# PY32F002BF1xP_START.net
KiCad netlist of a schematic drawn in Altium Designer
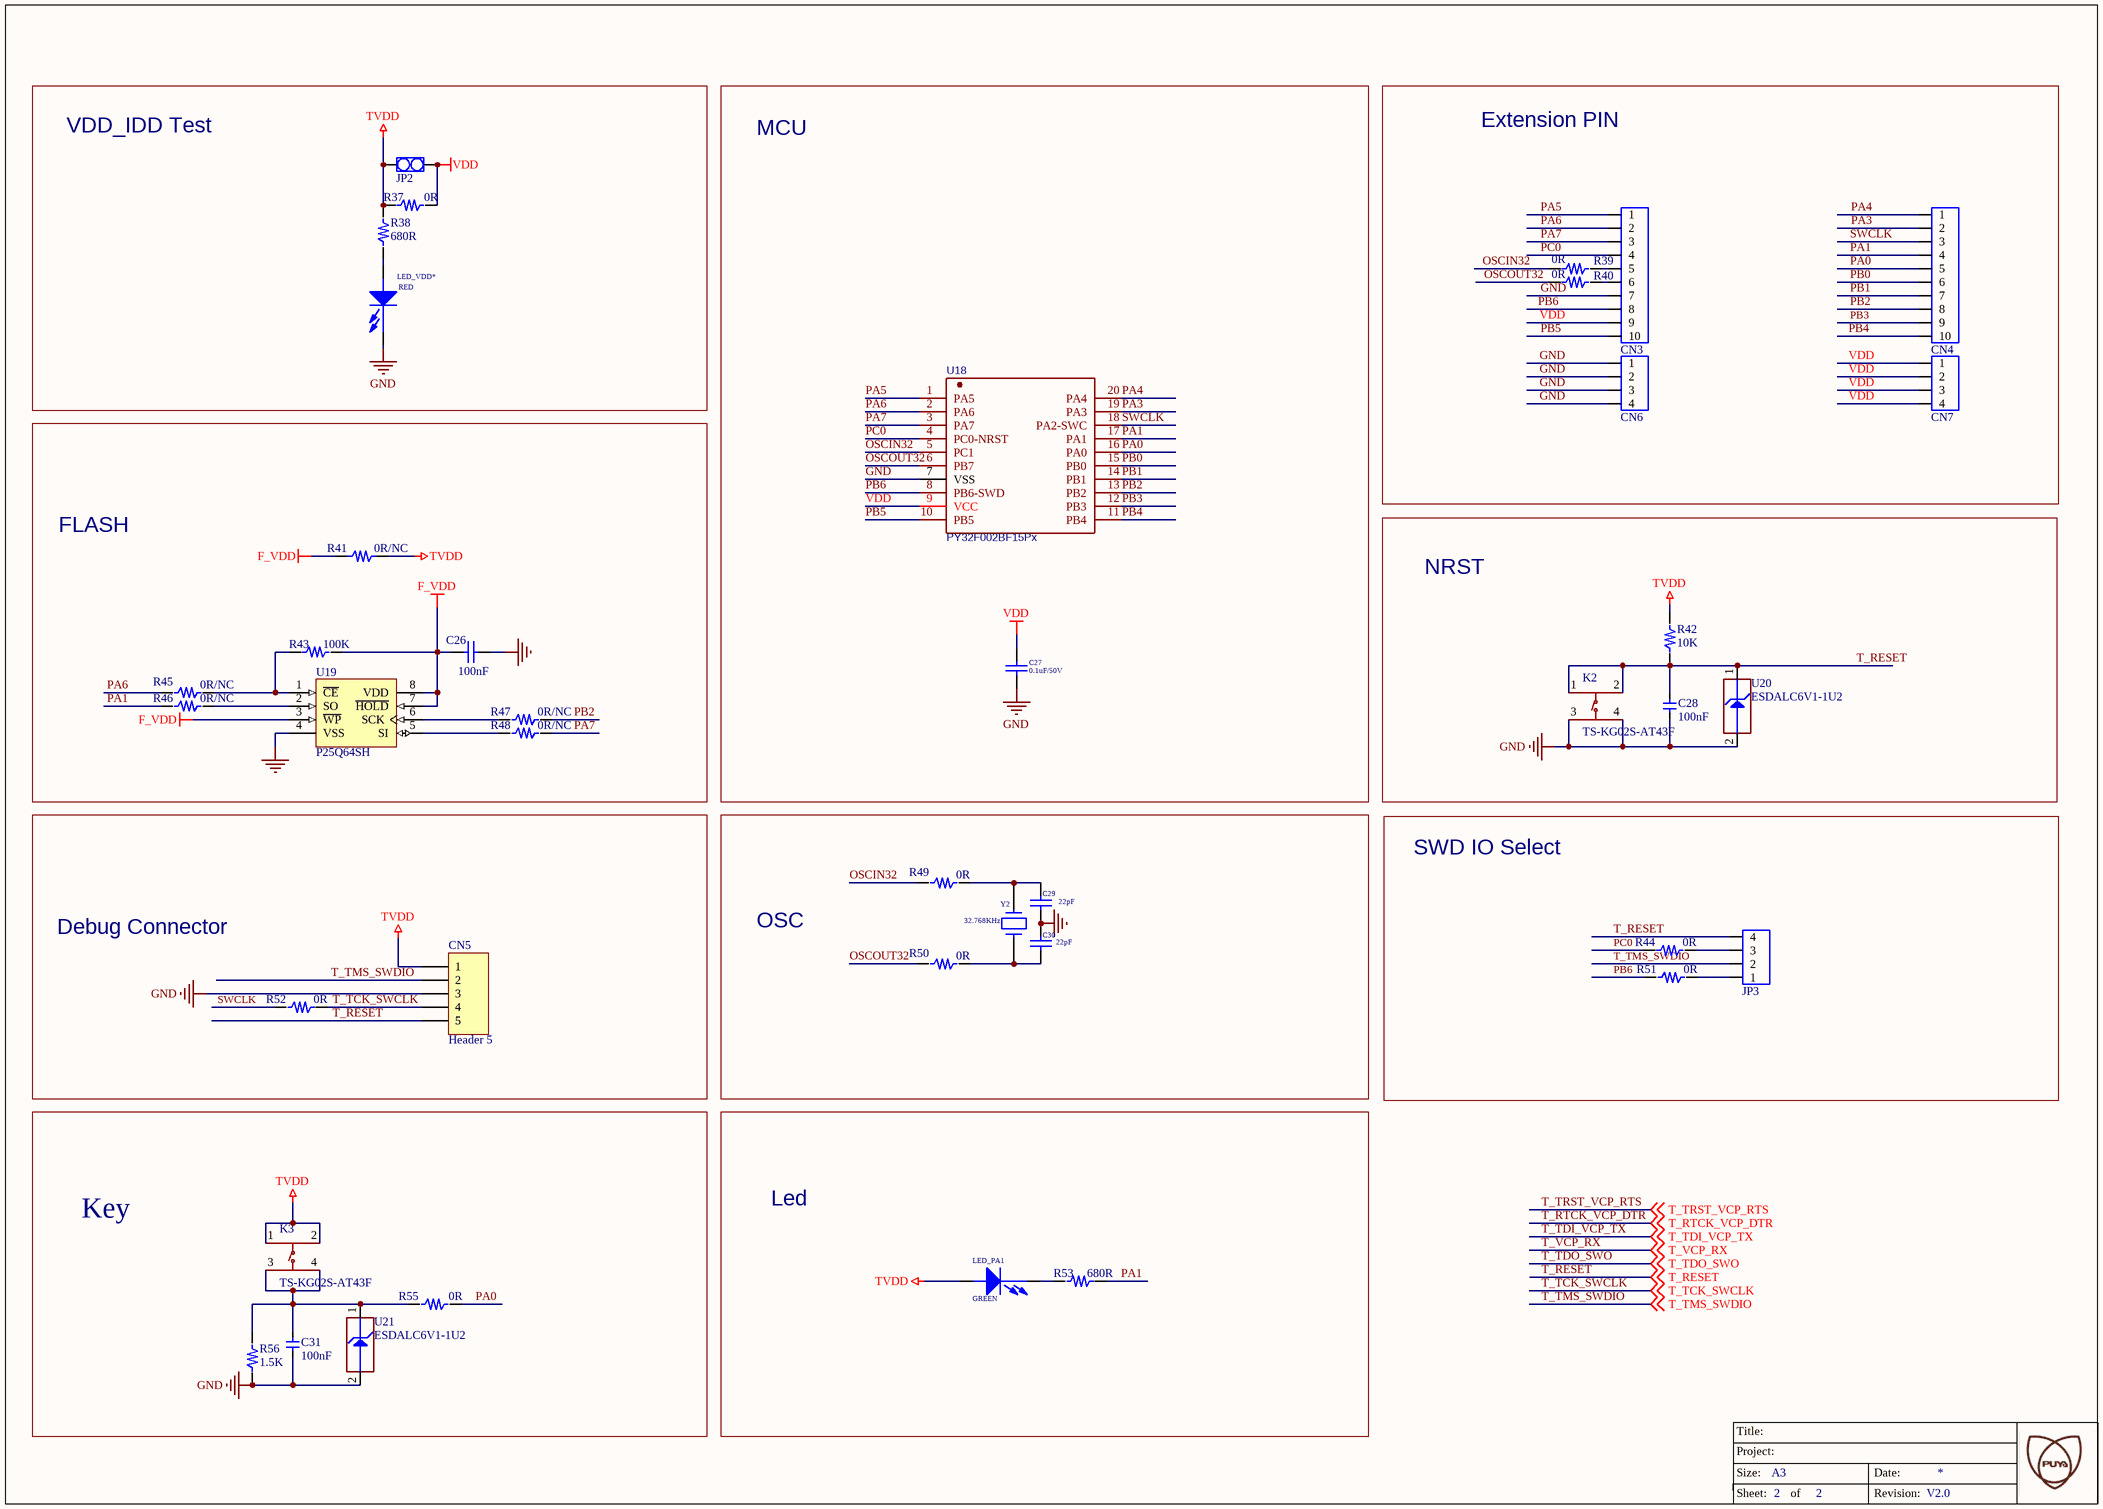
[diagram p0: PY32F002BF1xP_START.SchDoc]

(export (version "E")
  (design (tool "Eeschema 10.0.6"))
  (components
    (comp (ref "C26")
      (value "100nF")
      (footprint "C0603")
      (description "Capacitor (Semiconductor SIM Model)")
      (libsource (lib "PRO") (part "贴片高压陶瓷电容"))
    )
    (comp (ref "C27")
      (value "0.1uF/50V")
      (footprint "0603C")
      (description "Capacitor")
      (fields (field (name "PUBLISHER") "Altium Limited"))
      (libsource (lib "PY32F030_StartKit_V1.0") (part "CAP"))
    )
    (comp (ref "C28") (value "100nF") (footprint "C0603") (libsource (lib "ZqfAdLibrary") (part "C0603")))
    (comp (ref "C29")
      (value "22pF")
      (footprint "0603C")
      (description "Capacitor")
      (fields (field (name "PUBLISHER") "Altium Limited"))
      (libsource (lib "*") (part "Cap"))
    )
    (comp (ref "C30")
      (value "22pF")
      (footprint "0603C")
      (description "Capacitor")
      (fields (field (name "PUBLISHER") "Altium Limited"))
      (libsource (lib "*") (part "Cap"))
    )
    (comp (ref "C31") (value "100nF") (footprint "C0603") (libsource (lib "ZqfAdLibrary") (part "C0603")))
    (comp (ref "CN3") (value "CON10") (footprint "CON10") (libsource (lib "ZqfAdLibrary") (part "CON10")))
    (comp (ref "CN4") (value "CON10") (footprint "CON10") (libsource (lib "ZqfAdLibrary") (part "CON10")))
    (comp (ref "CN5")
      (value "Header 5")
      (footprint "HDR1X5")
      (description "Header, 5-Pin")
      (fields (field (name "PUBLISHER") "Altium Limited"))
      (libsource (lib "PY32F403x_64pin_PYLink_STK_V1.0") (part "Header 5"))
    )
    (comp (ref "CN6") (value "CON4") (footprint "CON4") (libsource (lib "ZqfAdLibrary") (part "CON4")))
    (comp (ref "CN7") (value "CON4") (footprint "CON4") (libsource (lib "ZqfAdLibrary") (part "CON4")))
    (comp (ref "JP2") (value "CON2") (footprint "CON2") (libsource (lib "ZqfAdLibrary") (part "CON2_DIP")))
    (comp (ref "JP3") (value "CON4") (footprint "CON4") (libsource (lib "ZqfAdLibrary") (part "CON4")))
    (comp (ref "K2")
      (value "TS-KG02S-AT43F")
      (footprint "SW-SMD_4P-L6.0-W6.0-P4.50-LS8.5")
      (fields (field (name "MANUFACTURER") "HANBO(汉博)"))
      (libsource (lib "altium-import") (part "root_0_TS-KG02S-AT43F_"))
    )
    (comp (ref "K3")
      (value "TS-KG02S-AT43F")
      (footprint "SW-SMD_4P-L6.0-W6.0-P4.50-LS8.5")
      (fields (field (name "MANUFACTURER") "HANBO(汉博)"))
      (libsource (lib "altium-import") (part "root_0_TS-KG02S-AT43F_"))
    )
    (comp (ref "LED_PA1")
      (value "GREEN")
      (footprint "0603_LED")
      (libsource (lib "Reliability EV board V1.0_1") (part "PDI-E803_Dup1"))
    )
    (comp (ref "LED_VDD*")
      (value "RED")
      (footprint "0603_LED")
      (libsource (lib "Reliability EV board V1.0_1") (part "PDI-E803_Dup1"))
    )
    (comp (ref "R37") (value "0R") (footprint "JP2_SMD") (libsource (lib "ZqfAdLibrary") (part "R0603")))
    (comp (ref "R38") (value "680R") (footprint "R0603") (libsource (lib "ZqfAdLibrary") (part "R0603")))
    (comp (ref "R39") (value "0R") (footprint "JP2_SMD") (libsource (lib "ZqfAdLibrary") (part "R0603")))
    (comp (ref "R40") (value "0R") (footprint "JP2_SMD") (libsource (lib "ZqfAdLibrary") (part "R0603")))
    (comp (ref "R41") (value "0R/NC") (footprint "JP2_SMD") (libsource (lib "ZqfAdLibrary") (part "R0603")))
    (comp (ref "R42") (value "10K") (footprint "R0603") (libsource (lib "ZqfAdLibrary") (part "R0603")))
    (comp (ref "R43") (value "100K") (footprint "R0603") (libsource (lib "ZqfAdLibrary") (part "R0603")))
    (comp (ref "R44") (value "0R") (footprint "JP2_SMD") (libsource (lib "ZqfAdLibrary") (part "R0603")))
    (comp (ref "R45") (value "0R/NC") (footprint "JP2_SMD") (libsource (lib "ZqfAdLibrary") (part "R0603")))
    (comp (ref "R46") (value "0R/NC") (footprint "JP2_SMD") (libsource (lib "ZqfAdLibrary") (part "R0603")))
    (comp (ref "R47") (value "0R/NC") (footprint "JP2_SMD") (libsource (lib "ZqfAdLibrary") (part "R0603")))
    (comp (ref "R48") (value "0R/NC") (footprint "JP2_SMD") (libsource (lib "ZqfAdLibrary") (part "R0603")))
    (comp (ref "R49") (value "0R") (footprint "JP2_SMD") (libsource (lib "ZqfAdLibrary") (part "R0603")))
    (comp (ref "R50") (value "0R") (footprint "JP2_SMD") (libsource (lib "ZqfAdLibrary") (part "R0603")))
    (comp (ref "R51") (value "0R") (footprint "JP2_SMD") (libsource (lib "ZqfAdLibrary") (part "R0603")))
    (comp (ref "R52") (value "0R") (footprint "JP2_SMD") (libsource (lib "ZqfAdLibrary") (part "R0603")))
    (comp (ref "R53") (value "680R") (footprint "R0603") (libsource (lib "ZqfAdLibrary") (part "R0603")))
    (comp (ref "R55") (value "0R") (footprint "JP2_SMD") (libsource (lib "ZqfAdLibrary") (part "R0603")))
    (comp (ref "R56") (value "1.5K") (footprint "R0603") (libsource (lib "ZqfAdLibrary") (part "R0603")))
    (comp (ref "U18")
      (value "PY32F002BF15Px")
      (footprint "TSSOP-20_L6.5-W4.4-P0.65-LS6.4-BL")
      (description "TSSOP20")
      (libsource (lib "Puya-MCU_V1.1") (part "PY32F002BF15Px"))
    )
    (comp (ref "U19")
      (value "P25Q64SH")
      (footprint "SOP-8P")
      (description "SST25VF010")
      (libsource (lib "PM3.00_Pro") (part "SST25VF010"))
    )
    (comp (ref "U20")
      (value "ESDALC6V1-1U2")
      (footprint "ESD_ST0201")
      (description "ESD protection 6V1")
      (fields
        (field (name "INTERNAL_PART_NUMBER") "MCD-00170")
        (field (name "MANUFACTURER") "STMICROELECTRONICS")
        (field (name "PROVIDED_BY") "Subcon")
      )
      (libsource (lib "PY32F403V1xT_START") (part "ESDALC6V1-1U2"))
    )
    (comp (ref "U21")
      (value "ESDALC6V1-1U2")
      (footprint "ESD_ST0201")
      (description "ESD protection 6V1")
      (fields
        (field (name "INTERNAL_PART_NUMBER") "MCD-00170")
        (field (name "MANUFACTURER") "STMICROELECTRONICS")
        (field (name "PROVIDED_BY") "Subcon")
      )
      (libsource (lib "PY32F403V1xT_START") (part "ESDALC6V1-1U2"))
    )
    (comp (ref "Y2")
      (value "32.768KHz")
      (footprint "CRYSTAL-SMD_L3.2-W1.5-1")
      (description "Crystal")
      (libsource (lib "PY32F002B_StartKit_V1.0") (part "CRYSTAL_1"))
    )
  )
  (nets
    (net (code "1") (name "/OSCIN32") (class "Default")
      (node (ref "R39") (pin "1") (pinfunction "1_1") (pintype "passive"))
      (node (ref "R49") (pin "2") (pinfunction "2_2") (pintype "passive"))
      (node (ref "U18") (pin "5") (pinfunction "PC1_5") (pintype "passive"))
    )
    (net (code "2") (name "/OSCOUT32") (class "Default")
      (node (ref "R40") (pin "1") (pinfunction "1_1") (pintype "passive"))
      (node (ref "R50") (pin "2") (pinfunction "2_2") (pintype "passive"))
      (node (ref "U18") (pin "6") (pinfunction "PB7_6") (pintype "passive"))
    )
    (net (code "3") (name "/PA0") (class "Default")
      (node (ref "CN4") (pin "5") (pinfunction "5_5") (pintype "passive"))
      (node (ref "R55") (pin "2") (pinfunction "2_2") (pintype "passive"))
      (node (ref "U18") (pin "16") (pinfunction "PA0_16") (pintype "passive"))
    )
    (net (code "4") (name "/PA1") (class "Default")
      (node (ref "CN4") (pin "4") (pinfunction "4_4") (pintype "passive"))
      (node (ref "R46") (pin "2") (pinfunction "2_2") (pintype "passive"))
      (node (ref "R53") (pin "2") (pinfunction "2_2") (pintype "passive"))
      (node (ref "U18") (pin "17") (pinfunction "PA1_17") (pintype "passive"))
    )
    (net (code "5") (name "/PA3") (class "Default")
      (node (ref "CN4") (pin "2") (pinfunction "2_2") (pintype "passive"))
      (node (ref "U18") (pin "19") (pinfunction "PA3_19") (pintype "passive"))
    )
    (net (code "6") (name "/PA4") (class "Default")
      (node (ref "CN4") (pin "1") (pinfunction "1_1") (pintype "passive"))
      (node (ref "U18") (pin "20") (pinfunction "PA4_20") (pintype "passive"))
    )
    (net (code "7") (name "/PA5") (class "Default")
      (node (ref "CN3") (pin "1") (pinfunction "1_1") (pintype "passive"))
      (node (ref "U18") (pin "1") (pinfunction "PA5_1") (pintype "passive"))
    )
    (net (code "8") (name "/PA6") (class "Default")
      (node (ref "CN3") (pin "2") (pinfunction "2_2") (pintype "passive"))
      (node (ref "R45") (pin "2") (pinfunction "2_2") (pintype "passive"))
      (node (ref "U18") (pin "2") (pinfunction "PA6_2") (pintype "passive"))
    )
    (net (code "9") (name "/PA7") (class "Default")
      (node (ref "CN3") (pin "3") (pinfunction "3_3") (pintype "passive"))
      (node (ref "R48") (pin "1") (pinfunction "1_1") (pintype "passive"))
      (node (ref "U18") (pin "3") (pinfunction "PA7_3") (pintype "passive"))
    )
    (net (code "10") (name "/PB0") (class "Default")
      (node (ref "CN4") (pin "6") (pinfunction "6_6") (pintype "passive"))
      (node (ref "U18") (pin "15") (pinfunction "PB0_15") (pintype "passive"))
    )
    (net (code "11") (name "/PB1") (class "Default")
      (node (ref "CN4") (pin "7") (pinfunction "7_7") (pintype "passive"))
      (node (ref "U18") (pin "14") (pinfunction "PB1_14") (pintype "passive"))
    )
    (net (code "12") (name "/PB2") (class "Default")
      (node (ref "CN4") (pin "8") (pinfunction "8_8") (pintype "passive"))
      (node (ref "R47") (pin "1") (pinfunction "1_1") (pintype "passive"))
      (node (ref "U18") (pin "13") (pinfunction "PB2_13") (pintype "passive"))
    )
    (net (code "13") (name "/PB3") (class "Default")
      (node (ref "CN4") (pin "9") (pinfunction "9_9") (pintype "passive"))
      (node (ref "U18") (pin "12") (pinfunction "PB3_12") (pintype "passive"))
    )
    (net (code "14") (name "/PB4") (class "Default")
      (node (ref "CN4") (pin "10") (pinfunction "10_10") (pintype "passive"))
      (node (ref "U18") (pin "11") (pinfunction "PB4_11") (pintype "passive"))
    )
    (net (code "15") (name "/PB5") (class "Default")
      (node (ref "CN3") (pin "10") (pinfunction "10_10") (pintype "passive"))
      (node (ref "U18") (pin "10") (pinfunction "PB5_10") (pintype "passive"))
    )
    (net (code "16") (name "/PB6") (class "Default")
      (node (ref "CN3") (pin "8") (pinfunction "8_8") (pintype "passive"))
      (node (ref "R51") (pin "2") (pinfunction "2_2") (pintype "passive"))
      (node (ref "U18") (pin "8") (pinfunction "PB6-SWD_8") (pintype "passive"))
    )
    (net (code "17") (name "/PC0") (class "Default")
      (node (ref "CN3") (pin "4") (pinfunction "4_4") (pintype "passive"))
      (node (ref "R44") (pin "2") (pinfunction "2_2") (pintype "passive"))
      (node (ref "U18") (pin "4") (pinfunction "PC0-NRST_4") (pintype "passive"))
    )
    (net (code "18") (name "/SWCLK") (class "Default")
      (node (ref "CN4") (pin "3") (pinfunction "3_3") (pintype "passive"))
      (node (ref "R52") (pin "2") (pinfunction "2_2") (pintype "passive"))
      (node (ref "U18") (pin "18") (pinfunction "PA2-SWC_18") (pintype "passive"))
    )
    (net (code "19") (name "F_VDD") (class "Default")
      (node (ref "C26") (pin "2") (pinfunction "2_2") (pintype "passive"))
      (node (ref "R41") (pin "2") (pinfunction "2_2") (pintype "passive"))
      (node (ref "R43") (pin "2") (pinfunction "2_2") (pintype "passive"))
      (node (ref "U19") (pin "3") (pinfunction "~{WP}_3") (pintype "input"))
      (node (ref "U19") (pin "7") (pinfunction "~{HOLD}_7") (pintype "input"))
      (node (ref "U19") (pin "8") (pinfunction "VDD_8") (pintype "power_in"))
    )
    (net (code "20") (name "GND") (class "Default")
      (node (ref "C26") (pin "1") (pinfunction "1_1") (pintype "passive"))
      (node (ref "C27") (pin "1") (pinfunction "1_1") (pintype "passive"))
      (node (ref "C28") (pin "1") (pinfunction "1_1") (pintype "passive"))
      (node (ref "C29") (pin "1") (pinfunction "1_1") (pintype "passive"))
      (node (ref "C30") (pin "2") (pinfunction "2_2") (pintype "passive"))
      (node (ref "C31") (pin "1") (pinfunction "1_1") (pintype "passive"))
      (node (ref "CN3") (pin "7") (pinfunction "7_7") (pintype "passive"))
      (node (ref "CN5") (pin "3") (pinfunction "3_3") (pintype "passive"))
      (node (ref "CN6") (pin "1") (pinfunction "1_1") (pintype "passive"))
      (node (ref "CN6") (pin "2") (pinfunction "2_2") (pintype "passive"))
      (node (ref "CN6") (pin "3") (pinfunction "3_3") (pintype "passive"))
      (node (ref "CN6") (pin "4") (pinfunction "4_4") (pintype "passive"))
      (node (ref "K2") (pin "3") (pinfunction "3_3") (pintype "passive"))
      (node (ref "K2") (pin "4") (pinfunction "4_4") (pintype "passive"))
      (node (ref "LED_VDD*") (pin "2") (pinfunction "CATHODE_2") (pintype "passive"))
      (node (ref "R56") (pin "1") (pinfunction "1_1") (pintype "passive"))
      (node (ref "U18") (pin "7") (pinfunction "VSS_7") (pintype "passive"))
      (node (ref "U19") (pin "4") (pinfunction "VSS_4") (pintype "power_in"))
      (node (ref "U20") (pin "2") (pinfunction "GND_2") (pintype "passive"))
      (node (ref "U21") (pin "2") (pinfunction "GND_2") (pintype "passive"))
    )
    (net (code "21") (name "Net-(C29-Pad2)") (class "Default")
      (node (ref "C29") (pin "2") (pinfunction "2_2") (pintype "passive"))
      (node (ref "R49") (pin "1") (pinfunction "1_1") (pintype "passive"))
      (node (ref "Y2") (pin "1") (pinfunction "1_1") (pintype "passive"))
    )
    (net (code "22") (name "Net-(C30-Pad1)") (class "Default")
      (node (ref "C30") (pin "1") (pinfunction "1_1") (pintype "passive"))
      (node (ref "R50") (pin "1") (pinfunction "1_1") (pintype "passive"))
      (node (ref "Y2") (pin "2") (pinfunction "2_2") (pintype "passive"))
    )
    (net (code "23") (name "Net-(CN3-Pad5)") (class "Default")
      (node (ref "CN3") (pin "5") (pinfunction "5_5") (pintype "passive"))
      (node (ref "R39") (pin "2") (pinfunction "2_2") (pintype "passive"))
    )
    (net (code "24") (name "Net-(CN3-Pad6)") (class "Default")
      (node (ref "CN3") (pin "6") (pinfunction "6_6") (pintype "passive"))
      (node (ref "R40") (pin "2") (pinfunction "2_2") (pintype "passive"))
    )
    (net (code "25") (name "Net-(JP3-Pad1)") (class "Default")
      (node (ref "JP3") (pin "1") (pinfunction "1_1") (pintype "passive"))
      (node (ref "R51") (pin "1") (pinfunction "1_1") (pintype "passive"))
    )
    (net (code "26") (name "Net-(JP3-Pad3)") (class "Default")
      (node (ref "JP3") (pin "3") (pinfunction "3_3") (pintype "passive"))
      (node (ref "R44") (pin "1") (pinfunction "1_1") (pintype "passive"))
    )
    (net (code "27") (name "Net-(LED_PA1-CATHODE)") (class "Default")
      (node (ref "LED_PA1") (pin "2") (pinfunction "CATHODE_2") (pintype "passive"))
      (node (ref "R53") (pin "1") (pinfunction "1_1") (pintype "passive"))
    )
    (net (code "28") (name "Net-(LED_VDD*-ANODE)") (class "Default")
      (node (ref "LED_VDD*") (pin "1") (pinfunction "ANODE_1") (pintype "passive"))
      (node (ref "R38") (pin "1") (pinfunction "1_1") (pintype "passive"))
    )
    (net (code "29") (name "Net-(U19-SCK)") (class "Default")
      (node (ref "R47") (pin "2") (pinfunction "2_2") (pintype "passive"))
      (node (ref "U19") (pin "6") (pinfunction "SCK_6") (pintype "input"))
    )
    (net (code "30") (name "Net-(U19-SI)") (class "Default")
      (node (ref "R48") (pin "2") (pinfunction "2_2") (pintype "passive"))
      (node (ref "U19") (pin "5") (pinfunction "SI_5") (pintype "bidirectional"))
    )
    (net (code "31") (name "Net-(U19-SO)") (class "Default")
      (node (ref "R46") (pin "1") (pinfunction "1_1") (pintype "passive"))
      (node (ref "U19") (pin "2") (pinfunction "SO_2") (pintype "input"))
    )
    (net (code "32") (name "Net-(U19-~{CE})") (class "Default")
      (node (ref "R43") (pin "1") (pinfunction "1_1") (pintype "passive"))
      (node (ref "R45") (pin "1") (pinfunction "1_1") (pintype "passive"))
      (node (ref "U19") (pin "1") (pinfunction "~{CE}_1") (pintype "input"))
    )
    (net (code "33") (name "Net-(U21-IO1)") (class "Default")
      (node (ref "C31") (pin "2") (pinfunction "2_2") (pintype "passive"))
      (node (ref "K3") (pin "3") (pinfunction "3_3") (pintype "passive"))
      (node (ref "K3") (pin "4") (pinfunction "4_4") (pintype "passive"))
      (node (ref "R55") (pin "1") (pinfunction "1_1") (pintype "passive"))
      (node (ref "R56") (pin "2") (pinfunction "2_2") (pintype "passive"))
      (node (ref "U21") (pin "1") (pinfunction "IO1_1") (pintype "passive"))
    )
    (net (code "34") (name "TVDD") (class "Default")
      (node (ref "CN5") (pin "1") (pinfunction "1_1") (pintype "passive"))
      (node (ref "JP2") (pin "1") (pinfunction "1_1") (pintype "passive"))
      (node (ref "K3") (pin "1") (pinfunction "1_1") (pintype "passive"))
      (node (ref "K3") (pin "2") (pinfunction "2_2") (pintype "passive"))
      (node (ref "LED_PA1") (pin "1") (pinfunction "ANODE_1") (pintype "passive"))
      (node (ref "R37") (pin "1") (pinfunction "1_1") (pintype "passive"))
      (node (ref "R38") (pin "2") (pinfunction "2_2") (pintype "passive"))
      (node (ref "R41") (pin "1") (pinfunction "1_1") (pintype "passive"))
      (node (ref "R42") (pin "1") (pinfunction "1_1") (pintype "passive"))
    )
    (net (code "35") (name "T_RESET") (class "Default")
      (node (ref "C28") (pin "2") (pinfunction "2_2") (pintype "passive"))
      (node (ref "CN5") (pin "5") (pinfunction "5_5") (pintype "passive"))
      (node (ref "JP3") (pin "4") (pinfunction "4_4") (pintype "passive"))
      (node (ref "K2") (pin "1") (pinfunction "1_1") (pintype "passive"))
      (node (ref "K2") (pin "2") (pinfunction "2_2") (pintype "passive"))
      (node (ref "R42") (pin "2") (pinfunction "2_2") (pintype "passive"))
      (node (ref "U20") (pin "1") (pinfunction "IO1_1") (pintype "passive"))
    )
    (net (code "37") (name "T_TCK_SWCLK") (class "Default")
      (node (ref "CN5") (pin "4") (pinfunction "4_4") (pintype "passive"))
      (node (ref "R52") (pin "1") (pinfunction "1_1") (pintype "passive"))
    )
    (net (code "40") (name "T_TMS_SWDIO") (class "Default")
      (node (ref "CN5") (pin "2") (pinfunction "2_2") (pintype "passive"))
      (node (ref "JP3") (pin "2") (pinfunction "2_2") (pintype "passive"))
    )
    (net (code "43") (name "VDD") (class "Default")
      (node (ref "C27") (pin "2") (pinfunction "2_2") (pintype "passive"))
      (node (ref "CN3") (pin "9") (pinfunction "9_9") (pintype "passive"))
      (node (ref "CN7") (pin "1") (pinfunction "1_1") (pintype "passive"))
      (node (ref "CN7") (pin "2") (pinfunction "2_2") (pintype "passive"))
      (node (ref "CN7") (pin "3") (pinfunction "3_3") (pintype "passive"))
      (node (ref "CN7") (pin "4") (pinfunction "4_4") (pintype "passive"))
      (node (ref "JP2") (pin "2") (pinfunction "2_2") (pintype "passive"))
      (node (ref "R37") (pin "2") (pinfunction "2_2") (pintype "passive"))
      (node (ref "U18") (pin "9") (pinfunction "VCC_9") (pintype "passive"))
    )
  )
)
